# MCU.net
KiCad netlist of a schematic drawn in Altium Designer
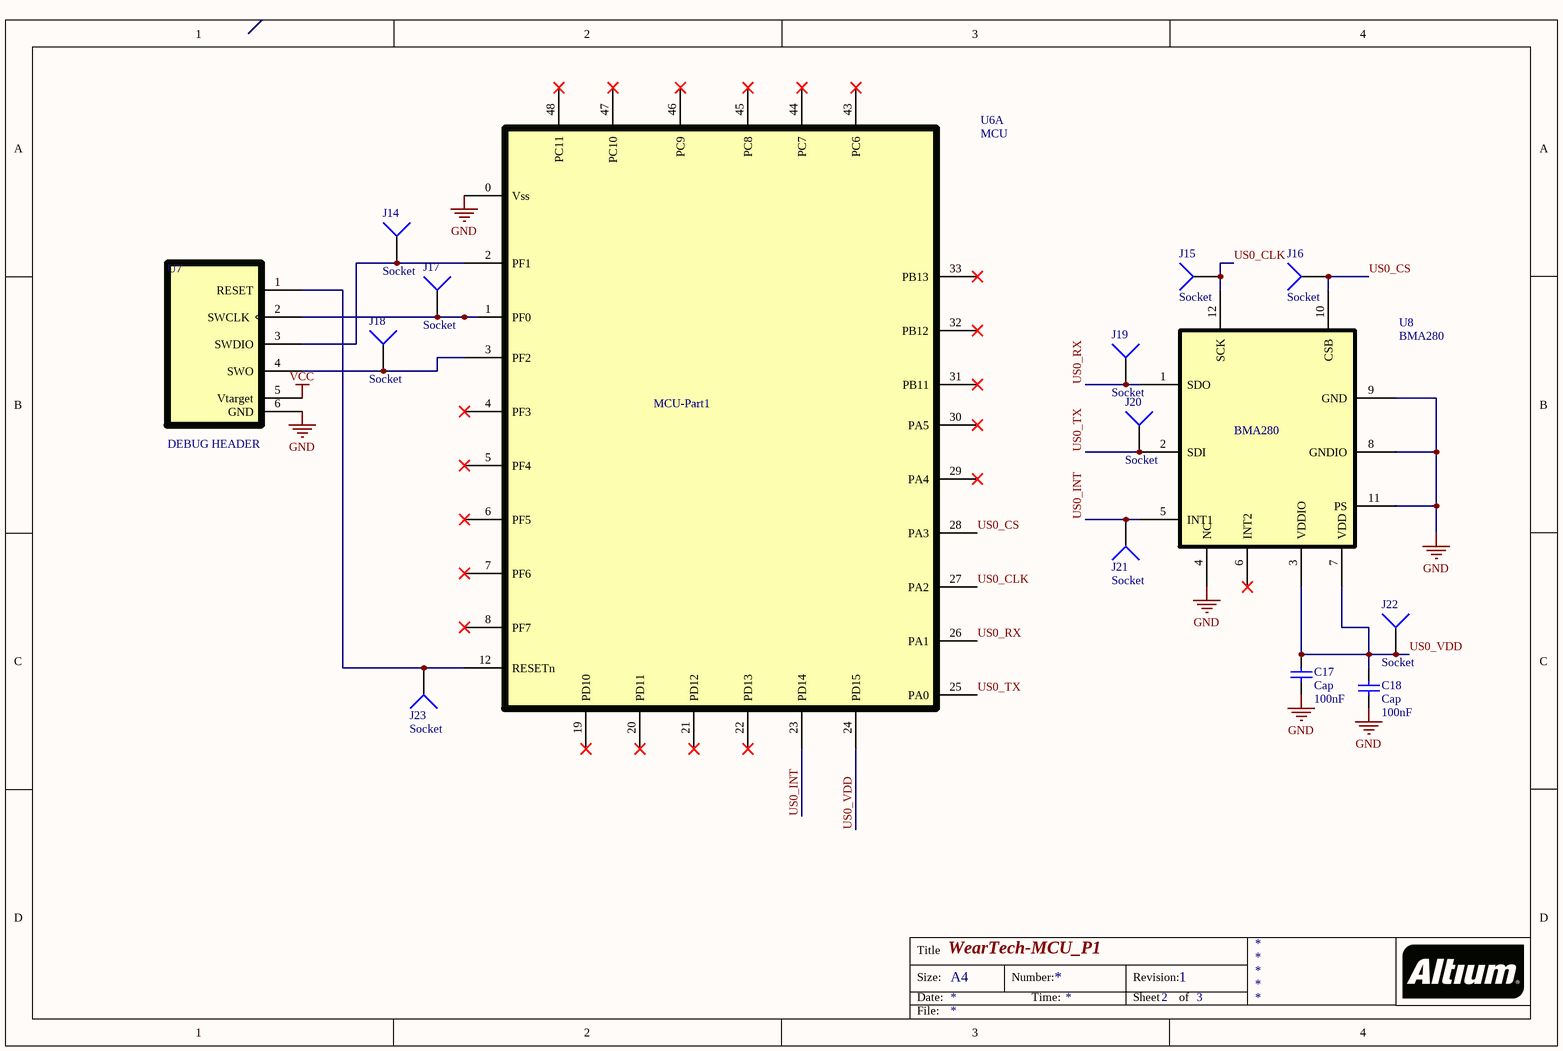
[diagram p0: MCU.SchDoc]

(export (version "E")
  (design (tool "Eeschema 10.0.6"))
  (components
    (comp (ref "C17")
      (value "Cap")
      (footprint "1608[0603]")
      (description "CAP CER 0.1UF 16V X7R 0603")
      (fields
        (field (name "ALTIUM_VALUE") "100nF")
        (field (name "MANUFACTURER") "Murata Electronics North America")
        (field (name "MANUFACTURER PART NUMBER") "GRM188R71C104KA01D")
      )
      (libsource (lib "Miscellaneous Devices") (part "Cap"))
    )
    (comp (ref "C18")
      (value "Cap")
      (footprint "1608[0603]")
      (description "CAP CER 0.1UF 16V X7R 0603")
      (fields
        (field (name "ALTIUM_VALUE") "100nF")
        (field (name "MANUFACTURER") "Murata Electronics North America")
        (field (name "MANUFACTURER PART NUMBER") "GRM188R71C104KA01D")
      )
      (libsource (lib "Miscellaneous Devices") (part "Cap"))
    )
    (comp (ref "J14")
      (value "Socket")
      (footprint "PIN1")
      (fields
        (field (name "MANUFACTURER") "Amphenol FCI")
        (field (name "MANUFACTURER PART NUMBER") "68000-200HLF")
        (field (name "DIGIKEY PART NUMBER") "609-5099-1-ND")
      )
      (libsource (lib "Miscellaneous Connectors") (part "Socket"))
    )
    (comp (ref "J15")
      (value "Socket")
      (footprint "PIN1")
      (fields
        (field (name "MANUFACTURER") "Amphenol FCI")
        (field (name "MANUFACTURER PART NUMBER") "68000-200HLF")
        (field (name "DIGIKEY PART NUMBER") "609-5099-1-ND")
      )
      (libsource (lib "Miscellaneous Connectors") (part "Socket"))
    )
    (comp (ref "J16")
      (value "Socket")
      (footprint "PIN1")
      (fields
        (field (name "MANUFACTURER") "Amphenol FCI")
        (field (name "MANUFACTURER PART NUMBER") "68000-200HLF")
        (field (name "DIGIKEY PART NUMBER") "609-5099-1-ND")
      )
      (libsource (lib "Miscellaneous Connectors") (part "Socket"))
    )
    (comp (ref "J17")
      (value "Socket")
      (footprint "PIN1")
      (fields
        (field (name "MANUFACTURER") "Amphenol FCI")
        (field (name "MANUFACTURER PART NUMBER") "68000-200HLF")
        (field (name "DIGIKEY PART NUMBER") "609-5099-1-ND")
      )
      (libsource (lib "Miscellaneous Connectors") (part "Socket"))
    )
    (comp (ref "J18")
      (value "Socket")
      (footprint "PIN1")
      (fields
        (field (name "MANUFACTURER") "Amphenol FCI")
        (field (name "MANUFACTURER PART NUMBER") "68000-200HLF")
        (field (name "DIGIKEY PART NUMBER") "609-5099-1-ND")
      )
      (libsource (lib "Miscellaneous Connectors") (part "Socket"))
    )
    (comp (ref "J19")
      (value "Socket")
      (footprint "PIN1")
      (fields
        (field (name "MANUFACTURER") "Amphenol FCI")
        (field (name "MANUFACTURER PART NUMBER") "68000-200HLF")
        (field (name "DIGIKEY PART NUMBER") "609-5099-1-ND")
      )
      (libsource (lib "Miscellaneous Connectors") (part "Socket"))
    )
    (comp (ref "J20")
      (value "Socket")
      (footprint "PIN1")
      (fields
        (field (name "MANUFACTURER") "Amphenol FCI")
        (field (name "MANUFACTURER PART NUMBER") "68000-200HLF")
        (field (name "DIGIKEY PART NUMBER") "609-5099-1-ND")
      )
      (libsource (lib "Miscellaneous Connectors") (part "Socket"))
    )
    (comp (ref "J21")
      (value "Socket")
      (footprint "PIN1")
      (fields
        (field (name "MANUFACTURER") "Amphenol FCI")
        (field (name "MANUFACTURER PART NUMBER") "68000-200HLF")
        (field (name "DIGIKEY PART NUMBER") "609-5099-1-ND")
      )
      (libsource (lib "Miscellaneous Connectors") (part "Socket"))
    )
    (comp (ref "J22")
      (value "Socket")
      (footprint "PIN1")
      (fields
        (field (name "MANUFACTURER") "Amphenol FCI")
        (field (name "MANUFACTURER PART NUMBER") "68000-200HLF")
        (field (name "DIGIKEY PART NUMBER") "609-5099-1-ND")
      )
      (libsource (lib "Miscellaneous Connectors") (part "Socket"))
    )
    (comp (ref "J23")
      (value "Socket")
      (footprint "PIN1")
      (fields
        (field (name "MANUFACTURER") "Amphenol FCI")
        (field (name "MANUFACTURER PART NUMBER") "68000-200HLF")
        (field (name "DIGIKEY PART NUMBER") "609-5099-1-ND")
      )
      (libsource (lib "Miscellaneous Connectors") (part "Socket"))
    )
    (comp (ref "U6")
      (value "MCU")
      (footprint "QFN50P700X700X90_HS-49N")
      (description "RF System on a Chip - SoC Blue Premium 19dBm 2.4G 512kB 64kB(RAM)")
      (fields
        (field (name "MANUFACTURER") "Silicon Labs")
        (field (name "MANUFACTURER PART NUMBER") "EFR32BG13P732F512GM48-C")
      )
      (libsource (lib "WearTechSchLib") (part "MCU"))
    )
    (comp (ref "U7")
      (value "DEBUG HEADER")
      (footprint "HDR1X6")
      (description "BERGSTRIP .100\" DR STRAIGHT")
      (fields
        (field (name "MANUFACTURER") "Amphenol FCI")
        (field (name "MANUFACTURER PART NUMBER") "68000-200HLF")
      )
      (libsource (lib "WearTechSchLib") (part "DEBUG HEADER"))
    )
    (comp (ref "U8")
      (value "BMA280")
      (footprint "QFN50P200X200X100-12N")
      (description "Accelerometers 3-Axis 2x2mm LGA-12 2g-16g prog 14-bit")
      (fields
        (field (name "MANUFACTURER") "Bosch Sensortec")
        (field (name "MOUSER PART NUMBER") "262-BMA280")
      )
      (libsource (lib "WearTechSchLib") (part "BMA280"))
    )
  )
  (nets
    (net (code "1") (name "/US0_CLK") (class "Default")
      (node (ref "J15") (pin "1") (pinfunction "1_1") (pintype "passive"))
      (node (ref "U6") (pin "27") (pinfunction "PA2_27") (pintype "passive"))
      (node (ref "U8") (pin "12") (pinfunction "SCK_12") (pintype "passive"))
    )
    (net (code "2") (name "/US0_CS") (class "Default")
      (node (ref "J16") (pin "1") (pinfunction "1_1") (pintype "passive"))
      (node (ref "U6") (pin "28") (pinfunction "PA3_28") (pintype "passive"))
      (node (ref "U8") (pin "10") (pinfunction "CSB_10") (pintype "passive"))
    )
    (net (code "3") (name "/US0_INT") (class "Default")
      (node (ref "J21") (pin "1") (pinfunction "1_1") (pintype "passive"))
      (node (ref "U6") (pin "23") (pinfunction "PD14_23") (pintype "passive"))
      (node (ref "U8") (pin "5") (pinfunction "INT1_5") (pintype "passive"))
    )
    (net (code "4") (name "/US0_RX") (class "Default")
      (node (ref "J19") (pin "1") (pinfunction "1_1") (pintype "passive"))
      (node (ref "U6") (pin "26") (pinfunction "PA1_26") (pintype "passive"))
      (node (ref "U8") (pin "1") (pinfunction "SDO_1") (pintype "passive"))
    )
    (net (code "5") (name "/US0_TX") (class "Default")
      (node (ref "J20") (pin "1") (pinfunction "1_1") (pintype "passive"))
      (node (ref "U6") (pin "25") (pinfunction "PA0_25") (pintype "passive"))
      (node (ref "U8") (pin "2") (pinfunction "SDI_2") (pintype "passive"))
    )
    (net (code "6") (name "/US0_VDD") (class "Default")
      (node (ref "C17") (pin "2") (pinfunction "2_2") (pintype "passive"))
      (node (ref "C18") (pin "2") (pinfunction "2_2") (pintype "passive"))
      (node (ref "J22") (pin "1") (pinfunction "1_1") (pintype "passive"))
      (node (ref "U6") (pin "24") (pinfunction "PD15_24") (pintype "passive"))
      (node (ref "U8") (pin "3") (pinfunction "VDDIO_3") (pintype "passive"))
      (node (ref "U8") (pin "7") (pinfunction "VDD_7") (pintype "passive"))
    )
    (net (code "7") (name "GND") (class "Default")
      (node (ref "C17") (pin "1") (pinfunction "1_1") (pintype "passive"))
      (node (ref "C18") (pin "1") (pinfunction "1_1") (pintype "passive"))
      (node (ref "U6") (pin "0") (pinfunction "Vss_0") (pintype "passive"))
      (node (ref "U7") (pin "6") (pinfunction "GND_6") (pintype "passive"))
      (node (ref "U8") (pin "11") (pinfunction "PS_11") (pintype "passive"))
      (node (ref "U8") (pin "4") (pinfunction "NC_4") (pintype "passive"))
      (node (ref "U8") (pin "8") (pinfunction "GNDIO_8") (pintype "passive"))
      (node (ref "U8") (pin "9") (pinfunction "GND_9") (pintype "passive"))
    )
    (net (code "8") (name "Net-(U6A-PF0)") (class "Default")
      (node (ref "J17") (pin "1") (pinfunction "1_1") (pintype "passive"))
      (node (ref "U6") (pin "1") (pinfunction "PF0_1") (pintype "passive"))
      (node (ref "U7") (pin "2") (pinfunction "SWCLK_2") (pintype "passive"))
    )
    (net (code "9") (name "Net-(U6A-PF1)") (class "Default")
      (node (ref "J14") (pin "1") (pinfunction "1_1") (pintype "passive"))
      (node (ref "U6") (pin "2") (pinfunction "PF1_2") (pintype "passive"))
      (node (ref "U7") (pin "3") (pinfunction "SWDIO_3") (pintype "passive"))
    )
    (net (code "10") (name "Net-(U6A-PF2)") (class "Default")
      (node (ref "J18") (pin "1") (pinfunction "1_1") (pintype "passive"))
      (node (ref "U6") (pin "3") (pinfunction "PF2_3") (pintype "passive"))
      (node (ref "U7") (pin "4") (pinfunction "SWO_4") (pintype "passive"))
    )
    (net (code "11") (name "Net-(U6A-RESETn)") (class "Default")
      (node (ref "J23") (pin "1") (pinfunction "1_1") (pintype "passive"))
      (node (ref "U6") (pin "12") (pinfunction "RESETn_12") (pintype "passive"))
      (node (ref "U7") (pin "1") (pinfunction "RESET_1") (pintype "passive"))
    )
    (net (code "12") (name "VCC") (class "Default")
      (node (ref "U7") (pin "5") (pinfunction "Vtarget_5") (pintype "passive"))
    )
    (net (code "13") (name "unconnected-(U6A-PA4-Pad29)") (class "Default")
      (node (ref "U6") (pin "29") (pinfunction "PA4_29") (pintype "passive+no_connect"))
    )
    (net (code "14") (name "unconnected-(U6A-PA5-Pad30)") (class "Default")
      (node (ref "U6") (pin "30") (pinfunction "PA5_30") (pintype "passive+no_connect"))
    )
    (net (code "15") (name "unconnected-(U6A-PB11-Pad31)") (class "Default")
      (node (ref "U6") (pin "31") (pinfunction "PB11_31") (pintype "passive+no_connect"))
    )
    (net (code "16") (name "unconnected-(U6A-PB12-Pad32)") (class "Default")
      (node (ref "U6") (pin "32") (pinfunction "PB12_32") (pintype "passive+no_connect"))
    )
    (net (code "17") (name "unconnected-(U6A-PB13-Pad33)") (class "Default")
      (node (ref "U6") (pin "33") (pinfunction "PB13_33") (pintype "passive+no_connect"))
    )
    (net (code "18") (name "unconnected-(U6A-PC6-Pad43)") (class "Default")
      (node (ref "U6") (pin "43") (pinfunction "PC6_43") (pintype "passive+no_connect"))
    )
    (net (code "19") (name "unconnected-(U6A-PC7-Pad44)") (class "Default")
      (node (ref "U6") (pin "44") (pinfunction "PC7_44") (pintype "passive+no_connect"))
    )
    (net (code "20") (name "unconnected-(U6A-PC8-Pad45)") (class "Default")
      (node (ref "U6") (pin "45") (pinfunction "PC8_45") (pintype "passive+no_connect"))
    )
    (net (code "21") (name "unconnected-(U6A-PC9-Pad46)") (class "Default")
      (node (ref "U6") (pin "46") (pinfunction "PC9_46") (pintype "passive+no_connect"))
    )
    (net (code "22") (name "unconnected-(U6A-PC10-Pad47)") (class "Default")
      (node (ref "U6") (pin "47") (pinfunction "PC10_47") (pintype "passive+no_connect"))
    )
    (net (code "23") (name "unconnected-(U6A-PC11-Pad48)") (class "Default")
      (node (ref "U6") (pin "48") (pinfunction "PC11_48") (pintype "passive+no_connect"))
    )
    (net (code "24") (name "unconnected-(U6A-PD10-Pad19)") (class "Default")
      (node (ref "U6") (pin "19") (pinfunction "PD10_19") (pintype "passive+no_connect"))
    )
    (net (code "25") (name "unconnected-(U6A-PD11-Pad20)") (class "Default")
      (node (ref "U6") (pin "20") (pinfunction "PD11_20") (pintype "passive+no_connect"))
    )
    (net (code "26") (name "unconnected-(U6A-PD12-Pad21)") (class "Default")
      (node (ref "U6") (pin "21") (pinfunction "PD12_21") (pintype "passive+no_connect"))
    )
    (net (code "27") (name "unconnected-(U6A-PD13-Pad22)") (class "Default")
      (node (ref "U6") (pin "22") (pinfunction "PD13_22") (pintype "passive+no_connect"))
    )
    (net (code "28") (name "unconnected-(U6A-PF3-Pad4)") (class "Default")
      (node (ref "U6") (pin "4") (pinfunction "PF3_4") (pintype "passive+no_connect"))
    )
    (net (code "29") (name "unconnected-(U6A-PF4-Pad5)") (class "Default")
      (node (ref "U6") (pin "5") (pinfunction "PF4_5") (pintype "passive+no_connect"))
    )
    (net (code "30") (name "unconnected-(U6A-PF5-Pad6)") (class "Default")
      (node (ref "U6") (pin "6") (pinfunction "PF5_6") (pintype "passive+no_connect"))
    )
    (net (code "31") (name "unconnected-(U6A-PF6-Pad7)") (class "Default")
      (node (ref "U6") (pin "7") (pinfunction "PF6_7") (pintype "passive+no_connect"))
    )
    (net (code "32") (name "unconnected-(U6A-PF7-Pad8)") (class "Default")
      (node (ref "U6") (pin "8") (pinfunction "PF7_8") (pintype "passive+no_connect"))
    )
    (net (code "33") (name "unconnected-(U8-INT2-Pad6)") (class "Default")
      (node (ref "U8") (pin "6") (pinfunction "INT2_6") (pintype "passive+no_connect"))
    )
  )
)
